# speed.net
KiCad netlist of a schematic drawn in EAGLE
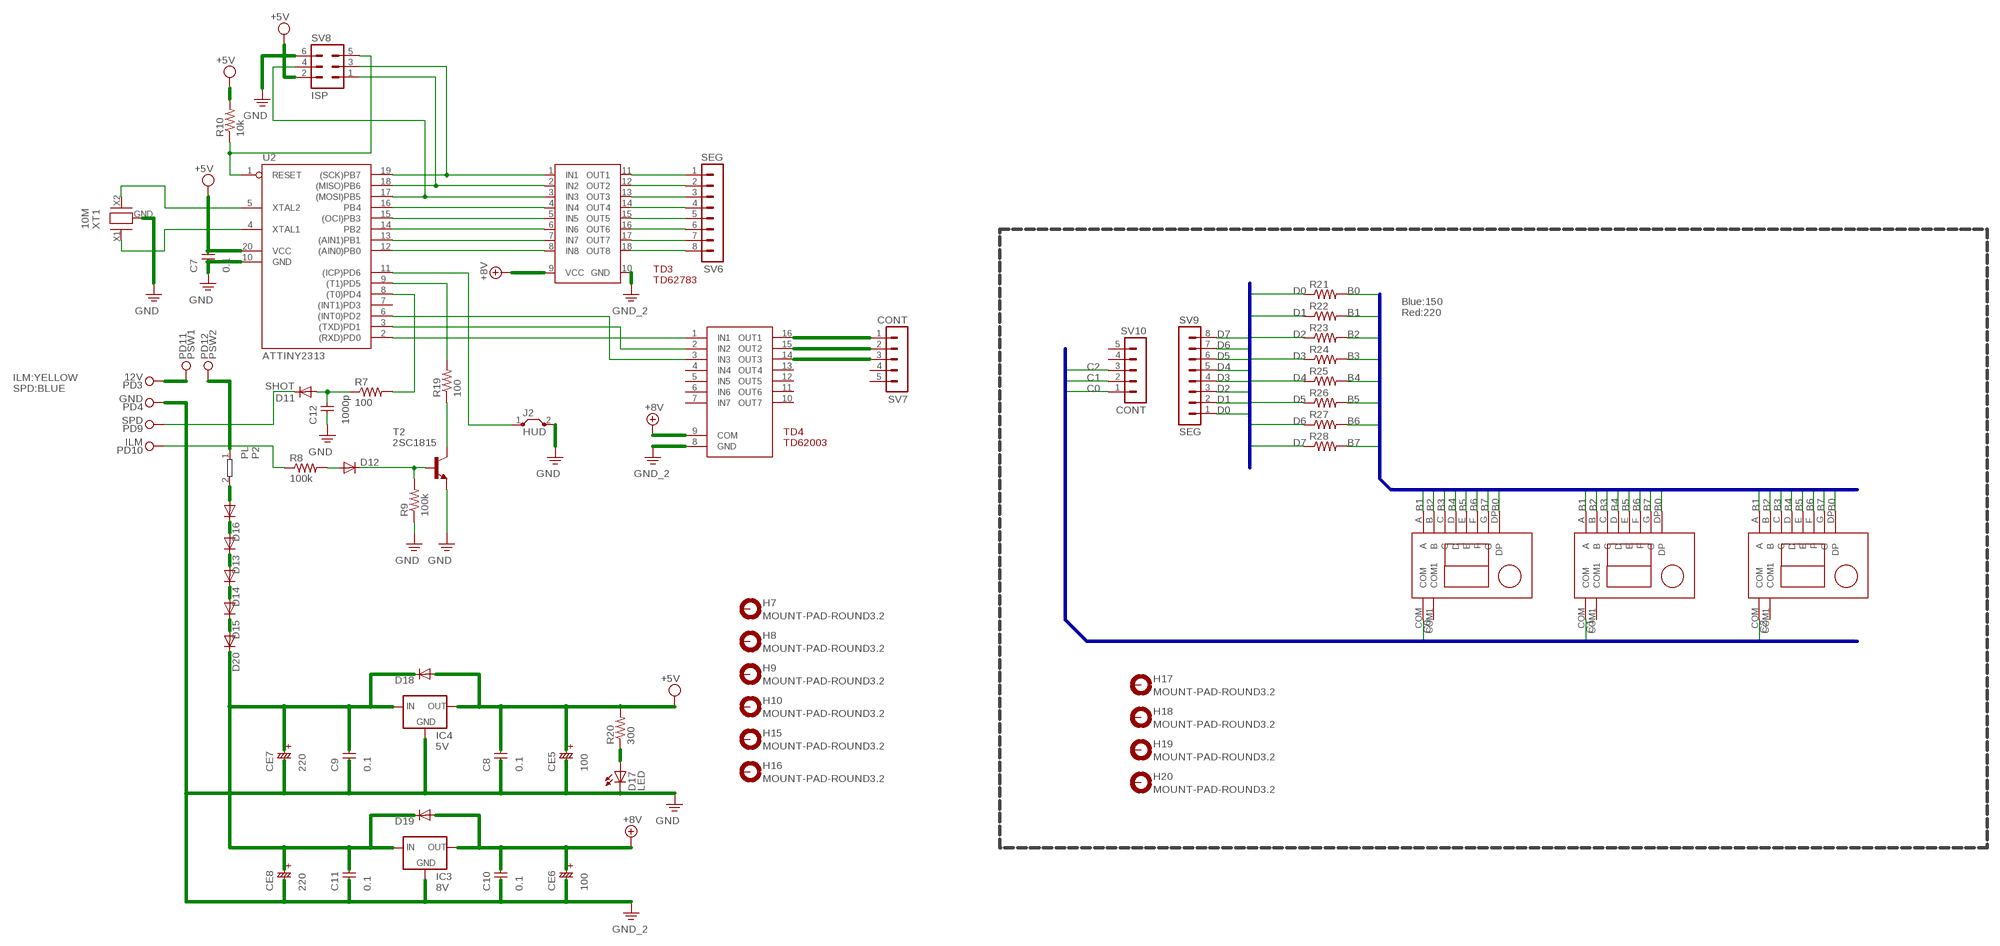
[diagram p0: schematic, sheet 1]

(export (version "E")
  (design (tool "Eeschema 10.0.6"))
  (components
    (comp (ref "C7")
      (value "0.1")
      (footprint "eagle-import:C-2,5")
      (libsource (lib "eagle-import") (part "C-2,5"))
    )
    (comp (ref "C8")
      (value "0.1")
      (footprint "eagle-import:C-2,5")
      (libsource (lib "eagle-import") (part "C-2,5"))
    )
    (comp (ref "C9")
      (value "0.1")
      (footprint "eagle-import:C-2,5")
      (libsource (lib "eagle-import") (part "C-2,5"))
    )
    (comp (ref "C10")
      (value "0.1")
      (footprint "eagle-import:C-2,5")
      (libsource (lib "eagle-import") (part "C-2,5"))
    )
    (comp (ref "C11")
      (value "0.1")
      (footprint "eagle-import:C-2,5")
      (libsource (lib "eagle-import") (part "C-2,5"))
    )
    (comp (ref "C12")
      (value "1000p")
      (footprint "eagle-import:C-2,5")
      (libsource (lib "eagle-import") (part "C-2,5"))
    )
    (comp (ref "CE5")
      (value "100")
      (footprint "eagle-import:ELC-2,5")
      (libsource (lib "eagle-import") (part "ELC-2,5"))
    )
    (comp (ref "CE6")
      (value "100")
      (footprint "eagle-import:ELC-2,5")
      (libsource (lib "eagle-import") (part "ELC-2,5"))
    )
    (comp (ref "CE7")
      (value "220")
      (footprint "eagle-import:ELC-5")
      (libsource (lib "eagle-import") (part "ELC-5"))
    )
    (comp (ref "CE8")
      (value "220")
      (footprint "eagle-import:ELC-5")
      (libsource (lib "eagle-import") (part "ELC-5"))
    )
    (comp (ref "D11")
      (value "SHOT")
      (footprint "eagle-import:0204V")
      (libsource (lib "eagle-import") (part "1N4004T"))
    )
    (comp (ref "D12")
      (value "1N4004\"")
      (footprint "eagle-import:DIP-2-10")
      (libsource (lib "eagle-import") (part "1N4004{dblquote}"))
    )
    (comp (ref "D13")
      (value "1N4004T")
      (footprint "eagle-import:0204V")
      (libsource (lib "eagle-import") (part "1N4004T"))
    )
    (comp (ref "D14")
      (value "1N4004T")
      (footprint "eagle-import:0204V")
      (libsource (lib "eagle-import") (part "1N4004T"))
    )
    (comp (ref "D15")
      (value "1N4004T")
      (footprint "eagle-import:0204V")
      (libsource (lib "eagle-import") (part "1N4004T"))
    )
    (comp (ref "D16")
      (value "1N4004T")
      (footprint "eagle-import:0204V")
      (libsource (lib "eagle-import") (part "1N4004T"))
    )
    (comp (ref "D17")
      (value "LED")
      (footprint "eagle-import:LED5MM")
      (libsource (lib "eagle-import") (part "LED5MM"))
    )
    (comp (ref "D18")
      (value "1N4004T")
      (footprint "eagle-import:0204V")
      (libsource (lib "eagle-import") (part "1N4004T"))
    )
    (comp (ref "D19")
      (value "1N4004T")
      (footprint "eagle-import:0204V")
      (libsource (lib "eagle-import") (part "1N4004T"))
    )
    (comp (ref "D20")
      (value "1N4004T")
      (footprint "eagle-import:0204V")
      (libsource (lib "eagle-import") (part "1N4004T"))
    )
    (comp (ref "H7")
      (value "MOUNT-PAD-ROUND3.2")
      (footprint "eagle-import:3,2-PAD")
      (libsource (lib "eagle-import") (part "MOUNT-PAD-ROUND3.2"))
    )
    (comp (ref "H8")
      (value "MOUNT-PAD-ROUND3.2")
      (footprint "eagle-import:3,2-PAD")
      (libsource (lib "eagle-import") (part "MOUNT-PAD-ROUND3.2"))
    )
    (comp (ref "H9")
      (value "MOUNT-PAD-ROUND3.2")
      (footprint "eagle-import:3,2-PAD")
      (libsource (lib "eagle-import") (part "MOUNT-PAD-ROUND3.2"))
    )
    (comp (ref "H10")
      (value "MOUNT-PAD-ROUND3.2")
      (footprint "eagle-import:3,2-PAD")
      (libsource (lib "eagle-import") (part "MOUNT-PAD-ROUND3.2"))
    )
    (comp (ref "H15")
      (value "MOUNT-PAD-ROUND3.2")
      (footprint "eagle-import:3,2-PAD")
      (libsource (lib "eagle-import") (part "MOUNT-PAD-ROUND3.2"))
    )
    (comp (ref "H16")
      (value "MOUNT-PAD-ROUND3.2")
      (footprint "eagle-import:3,2-PAD")
      (libsource (lib "eagle-import") (part "MOUNT-PAD-ROUND3.2"))
    )
    (comp (ref "H17")
      (value "MOUNT-PAD-ROUND3.2")
      (footprint "eagle-import:3,2-PAD")
      (libsource (lib "eagle-import") (part "MOUNT-PAD-ROUND3.2"))
    )
    (comp (ref "H18")
      (value "MOUNT-PAD-ROUND3.2")
      (footprint "eagle-import:3,2-PAD")
      (libsource (lib "eagle-import") (part "MOUNT-PAD-ROUND3.2"))
    )
    (comp (ref "H19")
      (value "MOUNT-PAD-ROUND3.2")
      (footprint "eagle-import:3,2-PAD")
      (libsource (lib "eagle-import") (part "MOUNT-PAD-ROUND3.2"))
    )
    (comp (ref "H20")
      (value "MOUNT-PAD-ROUND3.2")
      (footprint "eagle-import:3,2-PAD")
      (libsource (lib "eagle-import") (part "MOUNT-PAD-ROUND3.2"))
    )
    (comp (ref "IC3")
      (value "8V")
      (footprint "eagle-import:78XXL")
      (libsource (lib "eagle-import") (part "78XXLBACK"))
    )
    (comp (ref "IC4")
      (value "5V")
      (footprint "eagle-import:78XXS")
      (libsource (lib "eagle-import") (part "78XXS"))
    )
    (comp (ref "J2")
      (value "HUD")
      (footprint "eagle-import:JUMP2")
      (libsource (lib "eagle-import") (part "J2MM"))
    )
    (comp (ref "LED4")
      (value "C-551X")
      (footprint "eagle-import:7SEG-0.56")
      (libsource (lib "eagle-import") (part "C-551X"))
    )
    (comp (ref "LED5")
      (value "C-551X")
      (footprint "eagle-import:7SEG-0.56")
      (libsource (lib "eagle-import") (part "C-551X"))
    )
    (comp (ref "LED6")
      (value "C-551X")
      (footprint "eagle-import:7SEG-0.56")
      (libsource (lib "eagle-import") (part "C-551X"))
    )
    (comp (ref "P2")
      (value "PL")
      (footprint "eagle-import:0204_5")
      (libsource (lib "eagle-import") (part "POLISWITCH"))
    )
    (comp (ref "PD3")
      (value "12V")
      (footprint "eagle-import:CFPAD")
      (libsource (lib "eagle-import") (part "CPADF"))
    )
    (comp (ref "PD4")
      (value "GND")
      (footprint "eagle-import:CFPAD")
      (libsource (lib "eagle-import") (part "CPADF"))
    )
    (comp (ref "PD9")
      (value "SPD")
      (footprint "eagle-import:CFPAD")
      (libsource (lib "eagle-import") (part "CPADF"))
    )
    (comp (ref "PD10")
      (value "ILM")
      (footprint "eagle-import:CFPAD")
      (libsource (lib "eagle-import") (part "CPADF"))
    )
    (comp (ref "PD11")
      (value "PSW1")
      (footprint "eagle-import:CPPAD")
      (libsource (lib "eagle-import") (part "CPADP"))
    )
    (comp (ref "PD12")
      (value "PSW2")
      (footprint "eagle-import:CPPAD")
      (libsource (lib "eagle-import") (part "CPADP"))
    )
    (comp (ref "R7")
      (value "100")
      (footprint "eagle-import:0204_7")
      (libsource (lib "eagle-import") (part "RES7"))
    )
    (comp (ref "R8")
      (value "100k")
      (footprint "eagle-import:0204_7")
      (libsource (lib "eagle-import") (part "RES7"))
    )
    (comp (ref "R9")
      (value "100k")
      (footprint "eagle-import:0204_7")
      (libsource (lib "eagle-import") (part "RES7"))
    )
    (comp (ref "R10")
      (value "10k")
      (footprint "eagle-import:0204_7")
      (libsource (lib "eagle-import") (part "RES7"))
    )
    (comp (ref "R19")
      (value "100")
      (footprint "eagle-import:0204_7")
      (libsource (lib "eagle-import") (part "RES7"))
    )
    (comp (ref "R20")
      (value "300")
      (footprint "eagle-import:0204V")
      (libsource (lib "eagle-import") (part "RES_T"))
    )
    (comp (ref "R21")
      (value "RES7")
      (footprint "eagle-import:0204_7")
      (libsource (lib "eagle-import") (part "RES7"))
    )
    (comp (ref "R22")
      (value "RES7")
      (footprint "eagle-import:0204_7")
      (libsource (lib "eagle-import") (part "RES7"))
    )
    (comp (ref "R23")
      (value "RES7")
      (footprint "eagle-import:0204_7")
      (libsource (lib "eagle-import") (part "RES7"))
    )
    (comp (ref "R24")
      (value "RES7")
      (footprint "eagle-import:0204_7")
      (libsource (lib "eagle-import") (part "RES7"))
    )
    (comp (ref "R25")
      (value "RES7")
      (footprint "eagle-import:0204_7")
      (libsource (lib "eagle-import") (part "RES7"))
    )
    (comp (ref "R26")
      (value "RES7")
      (footprint "eagle-import:0204_7")
      (libsource (lib "eagle-import") (part "RES7"))
    )
    (comp (ref "R27")
      (value "RES7")
      (footprint "eagle-import:0204_7")
      (libsource (lib "eagle-import") (part "RES7"))
    )
    (comp (ref "R28")
      (value "RES7")
      (footprint "eagle-import:0204_7")
      (libsource (lib "eagle-import") (part "RES7"))
    )
    (comp (ref "SV6")
      (value "SEG")
      (footprint "eagle-import:MA08-1")
      (libsource (lib "eagle-import") (part "MA08-1"))
    )
    (comp (ref "SV7")
      (value "CONT")
      (footprint "eagle-import:MA05-1")
      (libsource (lib "eagle-import") (part "MA05-1"))
    )
    (comp (ref "SV8")
      (value "ISP")
      (footprint "eagle-import:ML6")
      (libsource (lib "eagle-import") (part "ML6"))
    )
    (comp (ref "SV9")
      (value "SEG")
      (footprint "eagle-import:MA08-1")
      (libsource (lib "eagle-import") (part "MA08-1"))
    )
    (comp (ref "SV10")
      (value "CONT")
      (footprint "eagle-import:MA05-1")
      (libsource (lib "eagle-import") (part "MA05-1"))
    )
    (comp (ref "T2")
      (value "2SC1815")
      (footprint "eagle-import:TO92")
      (libsource (lib "eagle-import") (part "2SC1815"))
    )
    (comp (ref "TD3")
      (value "TD62783")
      (footprint "eagle-import:DIP-18")
      (libsource (lib "eagle-import") (part "TD62783"))
    )
    (comp (ref "TD4")
      (value "TD62003")
      (footprint "eagle-import:DIP-16")
      (libsource (lib "eagle-import") (part "TD62003"))
    )
    (comp (ref "U2")
      (value "ATTINY2313")
      (footprint "eagle-import:DIP-20")
      (libsource (lib "eagle-import") (part "ATTINY2313"))
    )
    (comp (ref "XT1")
      (value "10M")
      (footprint "eagle-import:CELALOCK")
      (libsource (lib "eagle-import") (part "CELALOCK"))
    )
  )
  (nets
    (net (code "1") (name "+5V") (class "Default")
      (node (ref "C7") (pin "2") (pinfunction "P$2_2") (pintype "passive"))
      (node (ref "C8") (pin "2") (pinfunction "P$2_2") (pintype "passive"))
      (node (ref "CE5") (pin "PLUS") (pinfunction "PLUS_PLUS") (pintype "passive"))
      (node (ref "D18") (pin "1") (pinfunction "A_1") (pintype "passive"))
      (node (ref "IC4") (pin "OUT") (pinfunction "OUT_OUT") (pintype "passive"))
      (node (ref "R10") (pin "2") (pinfunction "2_2") (pintype "passive"))
      (node (ref "R20") (pin "2") (pinfunction "2_2") (pintype "passive"))
      (node (ref "SV8") (pin "2") (pinfunction "2_2") (pintype "passive"))
      (node (ref "U2") (pin "20") (pinfunction "VCC_20") (pintype "bidirectional"))
    )
    (net (code "2") (name "+8V") (class "Default")
      (node (ref "C10") (pin "2") (pinfunction "P$2_2") (pintype "passive"))
      (node (ref "CE6") (pin "PLUS") (pinfunction "PLUS_PLUS") (pintype "passive"))
      (node (ref "D19") (pin "1") (pinfunction "A_1") (pintype "passive"))
      (node (ref "IC3") (pin "IN") (pinfunction "OUT_IN") (pintype "passive"))
      (node (ref "TD3") (pin "9") (pinfunction "VCC_9") (pintype "bidirectional"))
      (node (ref "TD4") (pin "9") (pinfunction "COM_9") (pintype "bidirectional"))
    )
    (net (code "3") (name "/B0") (class "Default")
      (node (ref "LED4") (pin "DP") (pinfunction "DP_DP") (pintype "bidirectional"))
      (node (ref "LED5") (pin "DP") (pinfunction "DP_DP") (pintype "bidirectional"))
      (node (ref "LED6") (pin "DP") (pinfunction "DP_DP") (pintype "bidirectional"))
      (node (ref "R21") (pin "2") (pinfunction "2_2") (pintype "passive"))
    )
    (net (code "4") (name "/B1") (class "Default")
      (node (ref "LED4") (pin "A") (pinfunction "A_A") (pintype "bidirectional"))
      (node (ref "LED5") (pin "A") (pinfunction "A_A") (pintype "bidirectional"))
      (node (ref "LED6") (pin "A") (pinfunction "A_A") (pintype "bidirectional"))
      (node (ref "R22") (pin "2") (pinfunction "2_2") (pintype "passive"))
    )
    (net (code "5") (name "/B2") (class "Default")
      (node (ref "LED4") (pin "B") (pinfunction "B_B") (pintype "bidirectional"))
      (node (ref "LED5") (pin "B") (pinfunction "B_B") (pintype "bidirectional"))
      (node (ref "LED6") (pin "B") (pinfunction "B_B") (pintype "bidirectional"))
      (node (ref "R23") (pin "2") (pinfunction "2_2") (pintype "passive"))
    )
    (net (code "6") (name "/B3") (class "Default")
      (node (ref "LED4") (pin "C") (pinfunction "C_C") (pintype "bidirectional"))
      (node (ref "LED5") (pin "C") (pinfunction "C_C") (pintype "bidirectional"))
      (node (ref "LED6") (pin "C") (pinfunction "C_C") (pintype "bidirectional"))
      (node (ref "R24") (pin "2") (pinfunction "2_2") (pintype "passive"))
    )
    (net (code "7") (name "/B4") (class "Default")
      (node (ref "LED4") (pin "D") (pinfunction "D_D") (pintype "bidirectional"))
      (node (ref "LED5") (pin "D") (pinfunction "D_D") (pintype "bidirectional"))
      (node (ref "LED6") (pin "D") (pinfunction "D_D") (pintype "bidirectional"))
      (node (ref "R25") (pin "2") (pinfunction "2_2") (pintype "passive"))
    )
    (net (code "8") (name "/B5") (class "Default")
      (node (ref "LED4") (pin "E") (pinfunction "E_E") (pintype "bidirectional"))
      (node (ref "LED5") (pin "E") (pinfunction "E_E") (pintype "bidirectional"))
      (node (ref "LED6") (pin "E") (pinfunction "E_E") (pintype "bidirectional"))
      (node (ref "R26") (pin "2") (pinfunction "2_2") (pintype "passive"))
    )
    (net (code "9") (name "/B6") (class "Default")
      (node (ref "LED4") (pin "F") (pinfunction "F_F") (pintype "bidirectional"))
      (node (ref "LED5") (pin "F") (pinfunction "F_F") (pintype "bidirectional"))
      (node (ref "LED6") (pin "F") (pinfunction "F_F") (pintype "bidirectional"))
      (node (ref "R27") (pin "2") (pinfunction "2_2") (pintype "passive"))
    )
    (net (code "10") (name "/B7") (class "Default")
      (node (ref "LED4") (pin "G") (pinfunction "G_G") (pintype "bidirectional"))
      (node (ref "LED5") (pin "G") (pinfunction "G_G") (pintype "bidirectional"))
      (node (ref "LED6") (pin "G") (pinfunction "G_G") (pintype "bidirectional"))
      (node (ref "R28") (pin "2") (pinfunction "2_2") (pintype "passive"))
    )
    (net (code "11") (name "/C0") (class "Default")
      (node (ref "LED4") (pin "COM") (pinfunction "COM_COM") (pintype "bidirectional"))
      (node (ref "SV10") (pin "1") (pinfunction "1_1") (pintype "passive"))
    )
    (net (code "12") (name "/C1") (class "Default")
      (node (ref "LED5") (pin "COM") (pinfunction "COM_COM") (pintype "bidirectional"))
      (node (ref "SV10") (pin "2") (pinfunction "2_2") (pintype "passive"))
    )
    (net (code "13") (name "/C2") (class "Default")
      (node (ref "LED6") (pin "COM") (pinfunction "COM_COM") (pintype "bidirectional"))
      (node (ref "SV10") (pin "3") (pinfunction "3_3") (pintype "passive"))
    )
    (net (code "14") (name "/D0") (class "Default")
      (node (ref "R21") (pin "1") (pinfunction "1_1") (pintype "passive"))
      (node (ref "SV9") (pin "1") (pinfunction "1_1") (pintype "passive"))
    )
    (net (code "15") (name "/D1") (class "Default")
      (node (ref "R22") (pin "1") (pinfunction "1_1") (pintype "passive"))
      (node (ref "SV9") (pin "2") (pinfunction "2_2") (pintype "passive"))
    )
    (net (code "16") (name "/D2") (class "Default")
      (node (ref "R23") (pin "1") (pinfunction "1_1") (pintype "passive"))
      (node (ref "SV9") (pin "3") (pinfunction "3_3") (pintype "passive"))
    )
    (net (code "17") (name "/D3") (class "Default")
      (node (ref "R24") (pin "1") (pinfunction "1_1") (pintype "passive"))
      (node (ref "SV9") (pin "4") (pinfunction "4_4") (pintype "passive"))
    )
    (net (code "18") (name "/D4") (class "Default")
      (node (ref "R25") (pin "1") (pinfunction "1_1") (pintype "passive"))
      (node (ref "SV9") (pin "5") (pinfunction "5_5") (pintype "passive"))
    )
    (net (code "19") (name "/D5") (class "Default")
      (node (ref "R26") (pin "1") (pinfunction "1_1") (pintype "passive"))
      (node (ref "SV9") (pin "6") (pinfunction "6_6") (pintype "passive"))
    )
    (net (code "20") (name "/D6") (class "Default")
      (node (ref "R27") (pin "1") (pinfunction "1_1") (pintype "passive"))
      (node (ref "SV9") (pin "7") (pinfunction "7_7") (pintype "passive"))
    )
    (net (code "21") (name "/D7") (class "Default")
      (node (ref "R28") (pin "1") (pinfunction "1_1") (pintype "passive"))
      (node (ref "SV9") (pin "8") (pinfunction "8_8") (pintype "passive"))
    )
    (net (code "22") (name "GND") (class "Default")
      (node (ref "C10") (pin "1") (pinfunction "P$1_1") (pintype "passive"))
      (node (ref "C11") (pin "1") (pinfunction "P$1_1") (pintype "passive"))
      (node (ref "C12") (pin "1") (pinfunction "P$1_1") (pintype "passive"))
      (node (ref "C7") (pin "1") (pinfunction "P$1_1") (pintype "passive"))
      (node (ref "C8") (pin "1") (pinfunction "P$1_1") (pintype "passive"))
      (node (ref "C9") (pin "1") (pinfunction "P$1_1") (pintype "passive"))
      (node (ref "CE5") (pin "MAINAS") (pinfunction "MAINAS_MAINAS") (pintype "passive"))
      (node (ref "CE6") (pin "MAINAS") (pinfunction "MAINAS_MAINAS") (pintype "passive"))
      (node (ref "CE7") (pin "MAINAS") (pinfunction "MAINAS_MAINAS") (pintype "passive"))
      (node (ref "CE8") (pin "MAINAS") (pinfunction "MAINAS_MAINAS") (pintype "passive"))
      (node (ref "D17") (pin "K") (pinfunction "C_K") (pintype "passive"))
      (node (ref "IC3") (pin "GND") (pinfunction "GND_GND") (pintype "input"))
      (node (ref "IC4") (pin "GND") (pinfunction "GND_GND") (pintype "input"))
      (node (ref "J2") (pin "2") (pinfunction "2_2") (pintype "passive"))
      (node (ref "PD4") (pin "CPAD") (pinfunction "PAD_CPAD") (pintype "bidirectional"))
      (node (ref "R9") (pin "1") (pinfunction "1_1") (pintype "passive"))
      (node (ref "SV8") (pin "6") (pinfunction "6_6") (pintype "passive"))
      (node (ref "T2") (pin "3") (pinfunction "E_3") (pintype "passive"))
      (node (ref "TD3") (pin "10") (pinfunction "GND_10") (pintype "bidirectional"))
      (node (ref "TD4") (pin "8") (pinfunction "GND_8") (pintype "bidirectional"))
      (node (ref "U2") (pin "10") (pinfunction "GND_10") (pintype "bidirectional"))
      (node (ref "XT1") (pin "GND") (pinfunction "GND_GND") (pintype "bidirectional"))
    )
    (net (code "23") (name "Net-(C11-P$2)") (class "Default")
      (node (ref "C11") (pin "2") (pinfunction "P$2_2") (pintype "passive"))
      (node (ref "C9") (pin "2") (pinfunction "P$2_2") (pintype "passive"))
      (node (ref "CE7") (pin "PLUS") (pinfunction "PLUS_PLUS") (pintype "passive"))
      (node (ref "CE8") (pin "PLUS") (pinfunction "PLUS_PLUS") (pintype "passive"))
      (node (ref "D18") (pin "2") (pinfunction "C_2") (pintype "passive"))
      (node (ref "D19") (pin "2") (pinfunction "C_2") (pintype "passive"))
      (node (ref "D20") (pin "2") (pinfunction "C_2") (pintype "passive"))
      (node (ref "IC3") (pin "OUT") (pinfunction "IN_OUT") (pintype "input"))
      (node (ref "IC4") (pin "IN") (pinfunction "IN_IN") (pintype "input"))
    )
    (net (code "24") (name "Net-(C12-P$2)") (class "Default")
      (node (ref "C12") (pin "2") (pinfunction "P$2_2") (pintype "passive"))
      (node (ref "D11") (pin "1") (pinfunction "A_1") (pintype "passive"))
      (node (ref "R7") (pin "1") (pinfunction "1_1") (pintype "passive"))
    )
    (net (code "25") (name "Net-(D11-C)") (class "Default")
      (node (ref "D11") (pin "2") (pinfunction "C_2") (pintype "passive"))
      (node (ref "PD9") (pin "CPAD") (pinfunction "PAD_CPAD") (pintype "bidirectional"))
    )
    (net (code "26") (name "Net-(D12-PadA)") (class "Default")
      (node (ref "D12") (pin "A") (pinfunction "A_A") (pintype "passive"))
      (node (ref "R8") (pin "2") (pinfunction "2_2") (pintype "passive"))
    )
    (net (code "27") (name "Net-(D13-A)") (class "Default")
      (node (ref "D13") (pin "1") (pinfunction "A_1") (pintype "passive"))
      (node (ref "D16") (pin "2") (pinfunction "C_2") (pintype "passive"))
    )
    (net (code "28") (name "Net-(D13-C)") (class "Default")
      (node (ref "D13") (pin "2") (pinfunction "C_2") (pintype "passive"))
      (node (ref "D14") (pin "1") (pinfunction "A_1") (pintype "passive"))
    )
    (net (code "29") (name "Net-(D14-C)") (class "Default")
      (node (ref "D14") (pin "2") (pinfunction "C_2") (pintype "passive"))
      (node (ref "D15") (pin "1") (pinfunction "A_1") (pintype "passive"))
    )
    (net (code "30") (name "Net-(D15-C)") (class "Default")
      (node (ref "D15") (pin "2") (pinfunction "C_2") (pintype "passive"))
      (node (ref "D20") (pin "1") (pinfunction "A_1") (pintype "passive"))
    )
    (net (code "31") (name "Net-(D16-A)") (class "Default")
      (node (ref "D16") (pin "1") (pinfunction "A_1") (pintype "passive"))
      (node (ref "P2") (pin "2") (pinfunction "P2_2") (pintype "bidirectional"))
    )
    (net (code "32") (name "Net-(D17-PadA)") (class "Default")
      (node (ref "D17") (pin "A") (pinfunction "A_A") (pintype "passive"))
      (node (ref "R20") (pin "1") (pinfunction "1_1") (pintype "passive"))
    )
    (net (code "33") (name "Net-(P2-P1)") (class "Default")
      (node (ref "P2") (pin "1") (pinfunction "P1_1") (pintype "bidirectional"))
      (node (ref "PD12") (pin "CPPAD") (pinfunction "PAD_CPPAD") (pintype "bidirectional"))
    )
    (net (code "34") (name "Net-(PD10-PAD)") (class "Default")
      (node (ref "PD10") (pin "CPAD") (pinfunction "PAD_CPAD") (pintype "bidirectional"))
      (node (ref "R8") (pin "1") (pinfunction "1_1") (pintype "passive"))
    )
    (net (code "35") (name "Net-(PD11-PAD)") (class "Default")
      (node (ref "PD11") (pin "CPPAD") (pinfunction "PAD_CPPAD") (pintype "bidirectional"))
      (node (ref "PD3") (pin "CPAD") (pinfunction "PAD_CPAD") (pintype "bidirectional"))
    )
    (net (code "36") (name "Net-(T2-B)") (class "Default")
      (node (ref "D12") (pin "C") (pinfunction "C_C") (pintype "passive"))
      (node (ref "R9") (pin "2") (pinfunction "2_2") (pintype "passive"))
      (node (ref "T2") (pin "1") (pinfunction "B_1") (pintype "passive"))
    )
    (net (code "37") (name "Net-(T2-C)") (class "Default")
      (node (ref "R19") (pin "1") (pinfunction "1_1") (pintype "passive"))
      (node (ref "T2") (pin "2") (pinfunction "C_2") (pintype "passive"))
    )
    (net (code "38") (name "Net-(TD3-IN1)") (class "Default")
      (node (ref "SV8") (pin "3") (pinfunction "3_3") (pintype "passive"))
      (node (ref "TD3") (pin "1") (pinfunction "IN1_1") (pintype "bidirectional"))
      (node (ref "U2") (pin "19") (pinfunction "(SCK)PB7_19") (pintype "bidirectional"))
    )
    (net (code "39") (name "Net-(TD3-IN2)") (class "Default")
      (node (ref "SV8") (pin "1") (pinfunction "1_1") (pintype "passive"))
      (node (ref "TD3") (pin "2") (pinfunction "IN2_2") (pintype "bidirectional"))
      (node (ref "U2") (pin "18") (pinfunction "(MISO)PB6_18") (pintype "bidirectional"))
    )
    (net (code "40") (name "Net-(TD3-IN3)") (class "Default")
      (node (ref "SV8") (pin "4") (pinfunction "4_4") (pintype "passive"))
      (node (ref "TD3") (pin "3") (pinfunction "IN3_3") (pintype "bidirectional"))
      (node (ref "U2") (pin "17") (pinfunction "(MOSI)PB5_17") (pintype "bidirectional"))
    )
    (net (code "41") (name "Net-(TD3-IN4)") (class "Default")
      (node (ref "TD3") (pin "4") (pinfunction "IN4_4") (pintype "bidirectional"))
      (node (ref "U2") (pin "16") (pinfunction "PB4_16") (pintype "bidirectional"))
    )
    (net (code "42") (name "Net-(TD3-IN5)") (class "Default")
      (node (ref "TD3") (pin "5") (pinfunction "IN5_5") (pintype "bidirectional"))
      (node (ref "U2") (pin "15") (pinfunction "(OCI)PB3_15") (pintype "bidirectional"))
    )
    (net (code "43") (name "Net-(TD3-IN6)") (class "Default")
      (node (ref "TD3") (pin "6") (pinfunction "IN6_6") (pintype "bidirectional"))
      (node (ref "U2") (pin "14") (pinfunction "PB2_14") (pintype "bidirectional"))
    )
    (net (code "44") (name "Net-(TD3-IN7)") (class "Default")
      (node (ref "TD3") (pin "7") (pinfunction "IN7_7") (pintype "bidirectional"))
      (node (ref "U2") (pin "13") (pinfunction "(AIN1)PB1_13") (pintype "bidirectional"))
    )
    (net (code "45") (name "Net-(TD3-IN8)") (class "Default")
      (node (ref "TD3") (pin "8") (pinfunction "IN8_8") (pintype "bidirectional"))
      (node (ref "U2") (pin "12") (pinfunction "(AIN0)PB0_12") (pintype "bidirectional"))
    )
    (net (code "46") (name "Net-(TD3-OUT1)") (class "Default")
      (node (ref "SV6") (pin "1") (pinfunction "1_1") (pintype "passive"))
      (node (ref "TD3") (pin "11") (pinfunction "OUT1_11") (pintype "bidirectional"))
    )
    (net (code "47") (name "Net-(TD3-OUT2)") (class "Default")
      (node (ref "SV6") (pin "2") (pinfunction "2_2") (pintype "passive"))
      (node (ref "TD3") (pin "12") (pinfunction "OUT2_12") (pintype "bidirectional"))
    )
    (net (code "48") (name "Net-(TD3-OUT3)") (class "Default")
      (node (ref "SV6") (pin "3") (pinfunction "3_3") (pintype "passive"))
      (node (ref "TD3") (pin "13") (pinfunction "OUT3_13") (pintype "bidirectional"))
    )
    (net (code "49") (name "Net-(TD3-OUT4)") (class "Default")
      (node (ref "SV6") (pin "4") (pinfunction "4_4") (pintype "passive"))
      (node (ref "TD3") (pin "14") (pinfunction "OUT4_14") (pintype "bidirectional"))
    )
    (net (code "50") (name "Net-(TD3-OUT5)") (class "Default")
      (node (ref "SV6") (pin "5") (pinfunction "5_5") (pintype "passive"))
      (node (ref "TD3") (pin "15") (pinfunction "OUT5_15") (pintype "bidirectional"))
    )
    (net (code "51") (name "Net-(TD3-OUT6)") (class "Default")
      (node (ref "SV6") (pin "6") (pinfunction "6_6") (pintype "passive"))
      (node (ref "TD3") (pin "16") (pinfunction "OUT6_16") (pintype "bidirectional"))
    )
    (net (code "52") (name "Net-(TD3-OUT7)") (class "Default")
      (node (ref "SV6") (pin "7") (pinfunction "7_7") (pintype "passive"))
      (node (ref "TD3") (pin "17") (pinfunction "OUT7_17") (pintype "bidirectional"))
    )
    (net (code "53") (name "Net-(TD3-OUT8)") (class "Default")
      (node (ref "SV6") (pin "8") (pinfunction "8_8") (pintype "passive"))
      (node (ref "TD3") (pin "18") (pinfunction "OUT8_18") (pintype "bidirectional"))
    )
    (net (code "54") (name "Net-(TD4-IN1)") (class "Default")
      (node (ref "TD4") (pin "1") (pinfunction "IN1_1") (pintype "bidirectional"))
      (node (ref "U2") (pin "2") (pinfunction "(RXD)PD0_2") (pintype "bidirectional"))
    )
    (net (code "55") (name "Net-(TD4-IN2)") (class "Default")
      (node (ref "TD4") (pin "2") (pinfunction "IN2_2") (pintype "bidirectional"))
      (node (ref "U2") (pin "3") (pinfunction "(TXD)PD1_3") (pintype "bidirectional"))
    )
    (net (code "56") (name "Net-(TD4-IN3)") (class "Default")
      (node (ref "TD4") (pin "3") (pinfunction "IN3_3") (pintype "bidirectional"))
      (node (ref "U2") (pin "6") (pinfunction "(INT0)PD2_6") (pintype "bidirectional"))
    )
    (net (code "57") (name "Net-(TD4-OUT1)") (class "Default")
      (node (ref "SV7") (pin "1") (pinfunction "1_1") (pintype "passive"))
      (node (ref "TD4") (pin "16") (pinfunction "OUT1_16") (pintype "output"))
    )
    (net (code "58") (name "Net-(TD4-OUT2)") (class "Default")
      (node (ref "SV7") (pin "2") (pinfunction "2_2") (pintype "passive"))
      (node (ref "TD4") (pin "15") (pinfunction "OUT2_15") (pintype "output"))
    )
    (net (code "59") (name "Net-(TD4-OUT3)") (class "Default")
      (node (ref "SV7") (pin "3") (pinfunction "3_3") (pintype "passive"))
      (node (ref "TD4") (pin "14") (pinfunction "OUT3_14") (pintype "output"))
    )
    (net (code "60") (name "Net-(U2-(ICP)PD6)") (class "Default")
      (node (ref "J2") (pin "1") (pinfunction "1_1") (pintype "passive"))
      (node (ref "U2") (pin "11") (pinfunction "(ICP)PD6_11") (pintype "bidirectional"))
    )
    (net (code "61") (name "Net-(U2-(T0)PD4)") (class "Default")
      (node (ref "R7") (pin "2") (pinfunction "2_2") (pintype "passive"))
      (node (ref "U2") (pin "8") (pinfunction "(T0)PD4_8") (pintype "bidirectional"))
    )
    (net (code "62") (name "Net-(U2-(T1)PD5)") (class "Default")
      (node (ref "R19") (pin "2") (pinfunction "2_2") (pintype "passive"))
      (node (ref "U2") (pin "9") (pinfunction "(T1)PD5_9") (pintype "bidirectional"))
    )
    (net (code "63") (name "Net-(U2-RESET)") (class "Default")
      (node (ref "R10") (pin "1") (pinfunction "1_1") (pintype "passive"))
      (node (ref "SV8") (pin "5") (pinfunction "5_5") (pintype "passive"))
      (node (ref "U2") (pin "1") (pinfunction "RESET_1") (pintype "bidirectional"))
    )
    (net (code "64") (name "Net-(U2-XTAL1)") (class "Default")
      (node (ref "U2") (pin "4") (pinfunction "XTAL1_4") (pintype "bidirectional"))
      (node (ref "XT1") (pin "X1") (pinfunction "X1_X1") (pintype "bidirectional"))
    )
    (net (code "65") (name "Net-(U2-XTAL2)") (class "Default")
      (node (ref "U2") (pin "5") (pinfunction "XTAL2_5") (pintype "bidirectional"))
      (node (ref "XT1") (pin "X2") (pinfunction "X2_X2") (pintype "bidirectional"))
    )
    (net (code "66") (name "unconnected-(H7-MOUNT-PadB3,2)") (class "Default")
      (node (ref "H7") (pin "B3,2") (pinfunction "MOUNT_B3,2") (pintype "passive"))
    )
    (net (code "67") (name "unconnected-(H8-MOUNT-PadB3,2)") (class "Default")
      (node (ref "H8") (pin "B3,2") (pinfunction "MOUNT_B3,2") (pintype "passive"))
    )
    (net (code "68") (name "unconnected-(H9-MOUNT-PadB3,2)") (class "Default")
      (node (ref "H9") (pin "B3,2") (pinfunction "MOUNT_B3,2") (pintype "passive"))
    )
    (net (code "69") (name "unconnected-(H10-MOUNT-PadB3,2)") (class "Default")
      (node (ref "H10") (pin "B3,2") (pinfunction "MOUNT_B3,2") (pintype "passive"))
    )
    (net (code "70") (name "unconnected-(H15-MOUNT-PadB3,2)") (class "Default")
      (node (ref "H15") (pin "B3,2") (pinfunction "MOUNT_B3,2") (pintype "passive"))
    )
    (net (code "71") (name "unconnected-(H16-MOUNT-PadB3,2)") (class "Default")
      (node (ref "H16") (pin "B3,2") (pinfunction "MOUNT_B3,2") (pintype "passive"))
    )
    (net (code "72") (name "unconnected-(H17-MOUNT-PadB3,2)") (class "Default")
      (node (ref "H17") (pin "B3,2") (pinfunction "MOUNT_B3,2") (pintype "passive"))
    )
    (net (code "73") (name "unconnected-(H18-MOUNT-PadB3,2)") (class "Default")
      (node (ref "H18") (pin "B3,2") (pinfunction "MOUNT_B3,2") (pintype "passive"))
    )
    (net (code "74") (name "unconnected-(H19-MOUNT-PadB3,2)") (class "Default")
      (node (ref "H19") (pin "B3,2") (pinfunction "MOUNT_B3,2") (pintype "passive"))
    )
    (net (code "75") (name "unconnected-(H20-MOUNT-PadB3,2)") (class "Default")
      (node (ref "H20") (pin "B3,2") (pinfunction "MOUNT_B3,2") (pintype "passive"))
    )
    (net (code "76") (name "unconnected-(LED4-PadCOM1)") (class "Default")
      (node (ref "LED4") (pin "COM1") (pinfunction "COM1_COM1") (pintype "bidirectional"))
    )
    (net (code "77") (name "unconnected-(LED5-PadCOM1)") (class "Default")
      (node (ref "LED5") (pin "COM1") (pinfunction "COM1_COM1") (pintype "bidirectional"))
    )
    (net (code "78") (name "unconnected-(LED6-PadCOM1)") (class "Default")
      (node (ref "LED6") (pin "COM1") (pinfunction "COM1_COM1") (pintype "bidirectional"))
    )
    (net (code "79") (name "unconnected-(SV7-Pad4)") (class "Default")
      (node (ref "SV7") (pin "4") (pinfunction "4_4") (pintype "passive"))
    )
    (net (code "80") (name "unconnected-(SV7-Pad5)") (class "Default")
      (node (ref "SV7") (pin "5") (pinfunction "5_5") (pintype "passive"))
    )
    (net (code "81") (name "unconnected-(SV10-Pad4)") (class "Default")
      (node (ref "SV10") (pin "4") (pinfunction "4_4") (pintype "passive"))
    )
    (net (code "82") (name "unconnected-(SV10-Pad5)") (class "Default")
      (node (ref "SV10") (pin "5") (pinfunction "5_5") (pintype "passive"))
    )
    (net (code "83") (name "unconnected-(TD4-IN4-Pad4)") (class "Default")
      (node (ref "TD4") (pin "4") (pinfunction "IN4_4") (pintype "bidirectional"))
    )
    (net (code "84") (name "unconnected-(TD4-IN5-Pad5)") (class "Default")
      (node (ref "TD4") (pin "5") (pinfunction "IN5_5") (pintype "bidirectional"))
    )
    (net (code "85") (name "unconnected-(TD4-IN6-Pad6)") (class "Default")
      (node (ref "TD4") (pin "6") (pinfunction "IN6_6") (pintype "bidirectional"))
    )
    (net (code "86") (name "unconnected-(TD4-IN7-Pad7)") (class "Default")
      (node (ref "TD4") (pin "7") (pinfunction "IN7_7") (pintype "bidirectional"))
    )
    (net (code "87") (name "unconnected-(TD4-OUT4-Pad13)") (class "Default")
      (node (ref "TD4") (pin "13") (pinfunction "OUT4_13") (pintype "output"))
    )
    (net (code "88") (name "unconnected-(TD4-OUT5-Pad12)") (class "Default")
      (node (ref "TD4") (pin "12") (pinfunction "OUT5_12") (pintype "output"))
    )
    (net (code "89") (name "unconnected-(TD4-OUT6-Pad11)") (class "Default")
      (node (ref "TD4") (pin "11") (pinfunction "OUT6_11") (pintype "output"))
    )
    (net (code "90") (name "unconnected-(TD4-OUT7-Pad10)") (class "Default")
      (node (ref "TD4") (pin "10") (pinfunction "OUT7_10") (pintype "output"))
    )
    (net (code "91") (name "unconnected-(U2-(INT1)PD3-Pad7)") (class "Default")
      (node (ref "U2") (pin "7") (pinfunction "(INT1)PD3_7") (pintype "bidirectional"))
    )
  )
)
